# Sheet3.net
KiCad netlist of a schematic drawn in Altium Designer
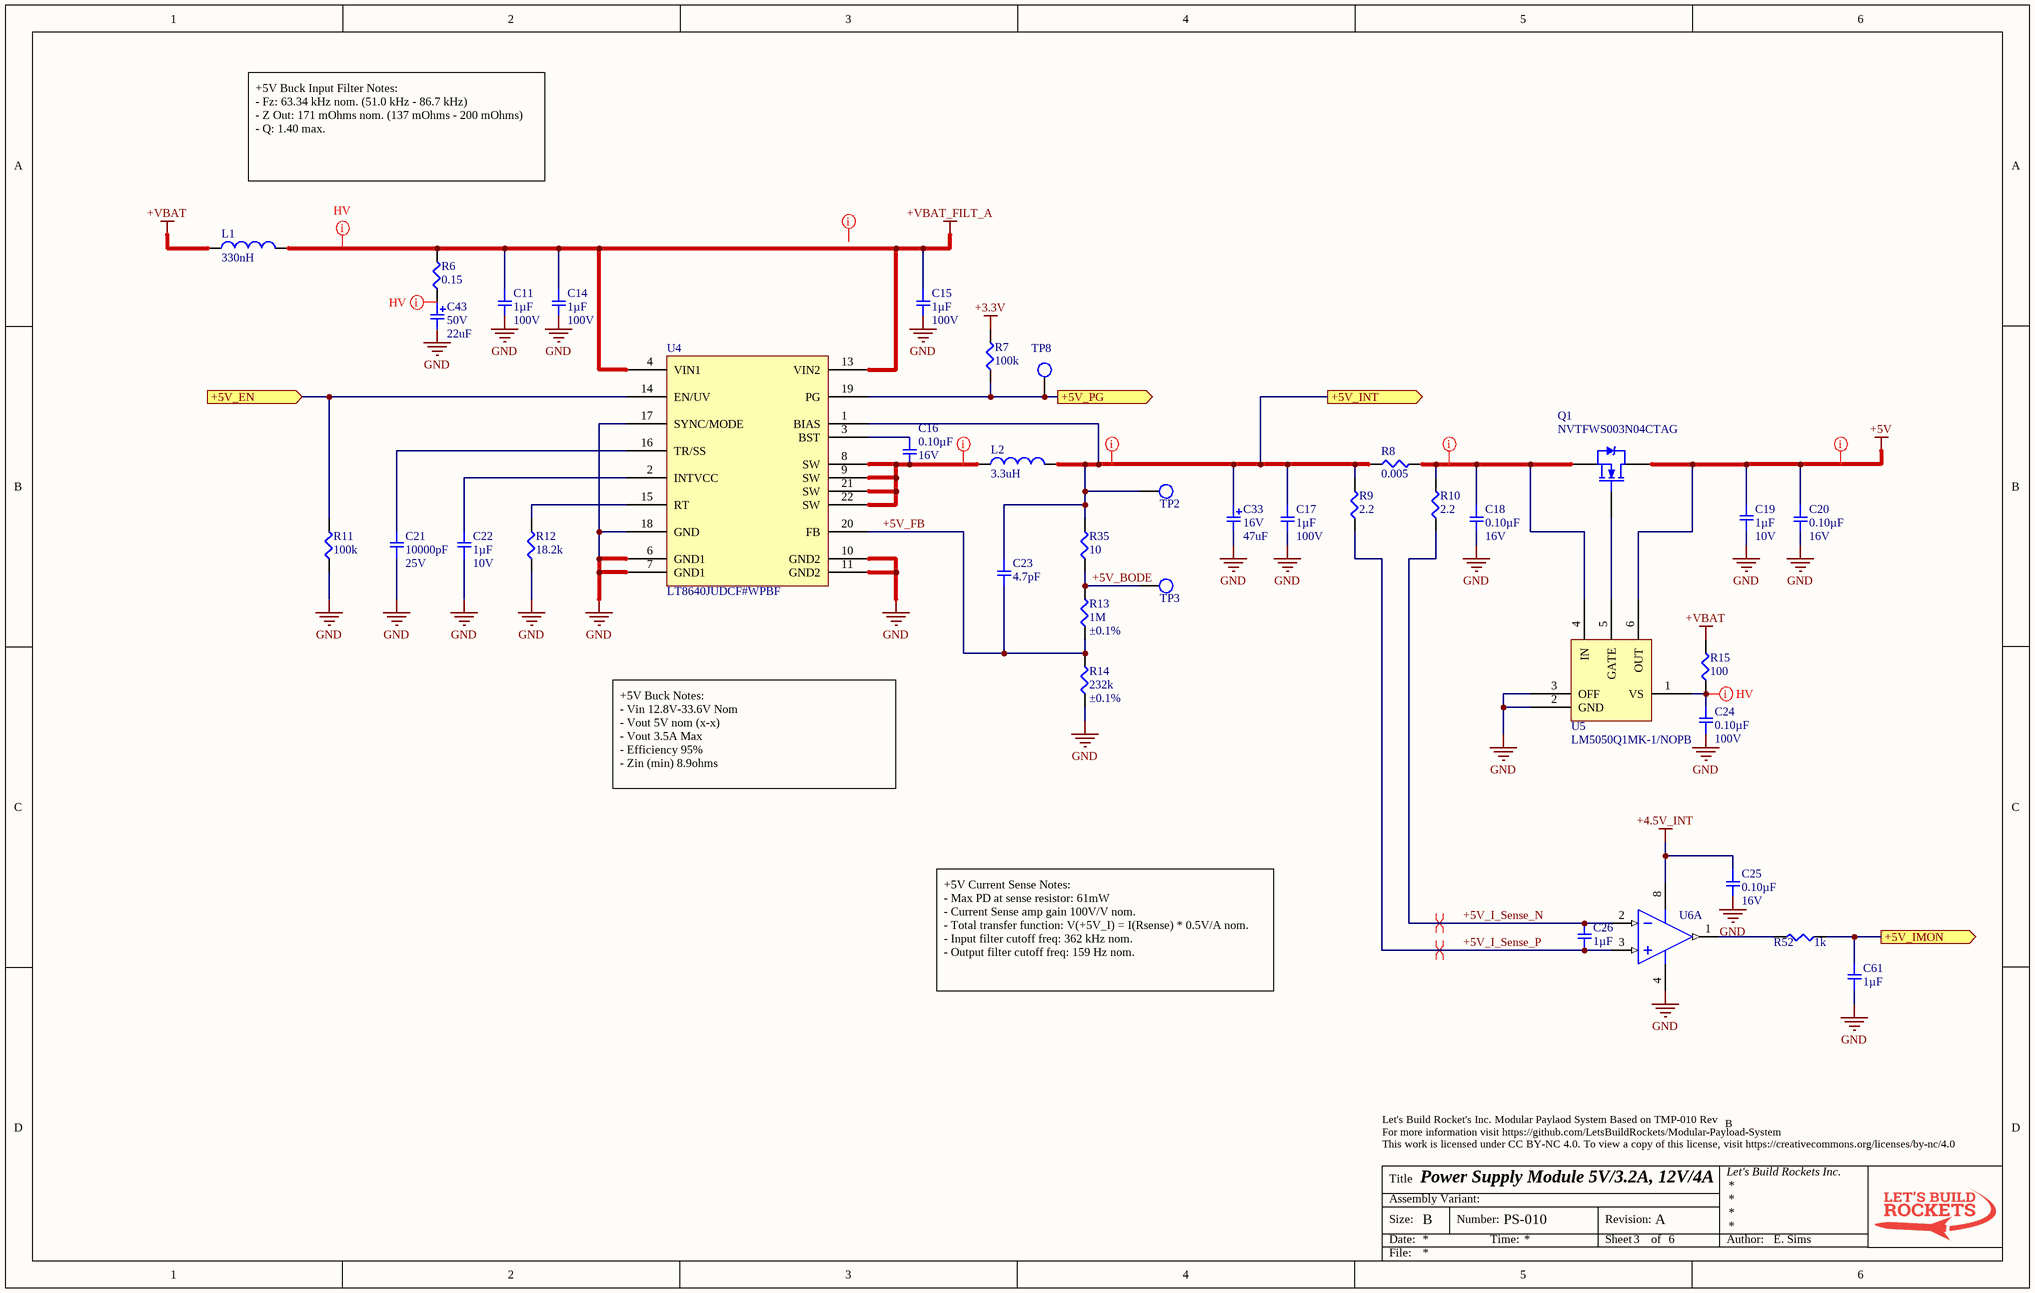
[diagram p0: Sheet3.SchDoc]

(export (version "E")
  (design (tool "Eeschema 10.0.6"))
  (components
    (comp (ref "C11")
      (value "1µF")
      (footprint "SMD-0805C")
      (description "CAP CER 1UF 100V X7S 0805")
      (fields
        (field (name "DIGI-KEY PART NUMBER") "490-10918-1-ND")
        (field (name "PART NUMBER") "GRJ21BC72A105KE11L")
        (field (name "VOLTAGE") "100V")
      )
      (libsource (lib "capacitor_murata_0805") (part "GRJ21BC72A105KE11L"))
    )
    (comp (ref "C14")
      (value "1µF")
      (footprint "SMD-0805C")
      (description "CAP CER 1UF 100V X7S 0805")
      (fields
        (field (name "DIGI-KEY PART NUMBER") "490-10918-1-ND")
        (field (name "PART NUMBER") "GRJ21BC72A105KE11L")
        (field (name "VOLTAGE") "100V")
      )
      (libsource (lib "capacitor_murata_0805") (part "GRJ21BC72A105KE11L"))
    )
    (comp (ref "C15")
      (value "1µF")
      (footprint "SMD-0805C")
      (description "CAP CER 1UF 100V X7S 0805")
      (fields
        (field (name "DIGI-KEY PART NUMBER") "490-10918-1-ND")
        (field (name "PART NUMBER") "GRJ21BC72A105KE11L")
        (field (name "VOLTAGE") "100V")
      )
      (libsource (lib "capacitor_murata_0805") (part "GRJ21BC72A105KE11L"))
    )
    (comp (ref "C16")
      (value "0.10µF")
      (footprint "SMD-0402C")
      (description "CAP CER 0.1UF 16V X7R 0402")
      (fields
        (field (name "DIGI-KEY PART NUMBER") "490-4759-1-ND")
        (field (name "PART NUMBER") "GCM155R71C104KA55D")
        (field (name "VOLTAGE") "16V")
      )
      (libsource (lib "capacitor_murata_0402") (part "GCM155R71C104KA55D"))
    )
    (comp (ref "C17")
      (value "1µF")
      (footprint "SMD-0805C")
      (description "CAP CER 1UF 100V X7S 0805")
      (fields
        (field (name "DIGI-KEY PART NUMBER") "490-10918-1-ND")
        (field (name "PART NUMBER") "GRJ21BC72A105KE11L")
        (field (name "VOLTAGE") "100V")
      )
      (libsource (lib "capacitor_murata_0805") (part "GRJ21BC72A105KE11L"))
    )
    (comp (ref "C18")
      (value "0.10µF")
      (footprint "SMD-0402C")
      (description "CAP CER 0.1UF 16V X7R 0402")
      (fields
        (field (name "DIGI-KEY PART NUMBER") "490-4759-1-ND")
        (field (name "PART NUMBER") "GCM155R71C104KA55D")
        (field (name "VOLTAGE") "16V")
      )
      (libsource (lib "capacitor_murata_0402") (part "GCM155R71C104KA55D"))
    )
    (comp (ref "C19")
      (value "1µF")
      (footprint "SMD-0402C")
      (description "CAP CER 1UF 10V X7S 0402")
      (fields
        (field (name "DIGI-KEY PART NUMBER") "490-13409-1-ND")
        (field (name "PART NUMBER") "GCM155C71A105KE38D")
        (field (name "VOLTAGE") "10V")
      )
      (libsource (lib "capacitor_murata_0402") (part "GCM155C71A105KE38D"))
    )
    (comp (ref "C20")
      (value "0.10µF")
      (footprint "SMD-0402C")
      (description "CAP CER 0.1UF 16V X7R 0402")
      (fields
        (field (name "DIGI-KEY PART NUMBER") "490-4759-1-ND")
        (field (name "PART NUMBER") "GCM155R71C104KA55D")
        (field (name "VOLTAGE") "16V")
      )
      (libsource (lib "capacitor_murata_0402") (part "GCM155R71C104KA55D"))
    )
    (comp (ref "C21")
      (value "10000pF")
      (footprint "SMD-0402C")
      (description "CAP CER 10000PF 25V X7R 0402")
      (fields
        (field (name "DIGI-KEY PART NUMBER") "490-6043-1-ND")
        (field (name "PART NUMBER") "GCM155R71E103KA37D")
        (field (name "VOLTAGE") "25V")
      )
      (libsource (lib "capacitor_murata_0402") (part "GCM155R71E103KA37D"))
    )
    (comp (ref "C22")
      (value "1µF")
      (footprint "SMD-0402C")
      (description "CAP CER 1UF 10V X7S 0402")
      (fields
        (field (name "DIGI-KEY PART NUMBER") "490-13409-1-ND")
        (field (name "PART NUMBER") "GCM155C71A105KE38D")
        (field (name "VOLTAGE") "10V")
      )
      (libsource (lib "capacitor_murata_0402") (part "GCM155C71A105KE38D"))
    )
    (comp (ref "C23")
      (value "4.7pF")
      (footprint "SMD-0402C")
      (description "CAP CER 4.7PF 50V NP0 0402")
      (fields
        (field (name "DIGI-KEY PART NUMBER") "490-12652-1-ND")
        (field (name "PART NUMBER") "GCM1555C1H4R7CA16D")
      )
      (libsource (lib "capacitor_murata_0402") (part "GCM1555C1H4R7CA16D"))
    )
    (comp (ref "C24")
      (value "0.10µF")
      (footprint "SMD-0603C")
      (description "CAP CER 0.1UF 100V X7R 0603")
      (fields
        (field (name "DIGI-KEY PART NUMBER") "490-3285-1-ND")
        (field (name "PART NUMBER") "GRM188R72A104KA35D")
        (field (name "VOLTAGE") "100V")
      )
      (libsource (lib "capacitor_murata_0603") (part "GRM188R72A104KA35D"))
    )
    (comp (ref "C25")
      (value "0.10µF")
      (footprint "SMD-0402C")
      (description "CAP CER 0.1UF 16V X7R 0402")
      (fields
        (field (name "DIGI-KEY PART NUMBER") "490-4759-1-ND")
        (field (name "PART NUMBER") "GCM155R71C104KA55D")
        (field (name "VOLTAGE") "16V")
      )
      (libsource (lib "capacitor_murata_0402") (part "GCM155R71C104KA55D"))
    )
    (comp (ref "C26")
      (value "1µF")
      (footprint "SMD-0402C")
      (description "CAP CER 1UF 10V X7S 0402")
      (fields
        (field (name "DIGI-KEY PART NUMBER") "490-13409-1-ND")
        (field (name "PART NUMBER") "GCM155C71A105KE38D")
      )
      (libsource (lib "capacitor_murata_0402") (part "GCM155C71A105KE38D"))
    )
    (comp (ref "C33")
      (value "47uF")
      (footprint "KEMET W - CAPMP7343X15N")
      (fields (field (name "VOLTAGE") "16V") (field (name "Comment") "T521W476M016ATE045"))
      (libsource (lib "KEMET") (part "T521W476M016ATE045"))
    )
    (comp (ref "C43")
      (value "22uF")
      (footprint "KEMET D - CAPMP7343X31N")
      (fields (field (name "VOLTAGE") "50V") (field (name "Comment") "T521D226M050ATE090"))
      (libsource (lib "KEMET") (part "T521D226M050ATE090"))
    )
    (comp (ref "C61")
      (value "1µF")
      (footprint "SMD-0402C")
      (description "CAP CER 1UF 10V X7S 0402")
      (fields
        (field (name "DIGI-KEY PART NUMBER") "490-13409-1-ND")
        (field (name "PART NUMBER") "GCM155C71A105KE38D")
      )
      (libsource (lib "capacitor_murata_0402") (part "GCM155C71A105KE38D"))
    )
    (comp (ref "L1")
      (value "330nH")
      (footprint "INDM4040X21N (XGL4020)")
      (fields (field (name "Comment") "XGL4020-331ME"))
      (libsource (lib "ModularPayload") (part "XGL4020-331ME"))
    )
    (comp (ref "L2")
      (value "3.3uH")
      (footprint "INDM7050X50N (Wurth)")
      (fields (field (name "TOLERANCE") "20%") (field (name "Comment") "744314330"))
      (libsource (lib "ModularPayload") (part "744314330"))
    )
    (comp (ref "Q1")
      (value "NVTFWS003N04CTAG")
      (footprint "DFN065P305X80-8N")
      (libsource (lib "ModularPayload") (part "NVTFWS003N04CTAG"))
    )
    (comp (ref "R6")
      (value "0.15")
      (footprint "SMD-0603-RES")
      (description "RES SMD 0.15 OHM 5% 1/4W 0603")
      (fields (field (name "PART NUMBER") "ERJ-3BSJR15V") (field (name "DIGI-KEY PART NUMBER") "P17248CT-ND"))
      (libsource (lib "Panasonic_ERJ_0603") (part "ERJ-3BSJR15V"))
    )
    (comp (ref "R7")
      (value "100k")
      (footprint "SMD-0402-RES")
      (description "RES SMD 100K OHM 5% 1/10W 0402")
      (fields (field (name "PART NUMBER") "ERJ-2GEJ104X") (field (name "DIGI-KEY PART NUMBER") "P100KJCT-ND"))
      (libsource (lib "Panasonic_ERJ_0402") (part "ERJ-2GEJ104X"))
    )
    (comp (ref "R8")
      (value "0.005")
      (footprint "SMD-0603-RES")
      (description "RES SMD 0.005 OHM 1% 1/4W 0603")
      (fields
        (field (name "PART NUMBER") "ERJ-3LWFR005V")
        (field (name "DIGI-KEY PART NUMBER") "P19182CT-ND")
      )
      (libsource (lib "Panasonic_ERJ_0603") (part "ERJ-3LWFR005V"))
    )
    (comp (ref "R9")
      (value "2.2")
      (footprint "SMD-0603-RES")
      (description "RES SMD 2.2 OHM 1% 1/10W 0603")
      (fields (field (name "PART NUMBER") "ERJ-3RQF2R2V") (field (name "DIGI-KEY PART NUMBER") "P2.2AJCT-ND"))
      (libsource (lib "Panasonic_ERJ_0603") (part "ERJ-3RQF2R2V"))
    )
    (comp (ref "R10")
      (value "2.2")
      (footprint "SMD-0603-RES")
      (description "RES SMD 2.2 OHM 1% 1/10W 0603")
      (fields (field (name "PART NUMBER") "ERJ-3RQF2R2V") (field (name "DIGI-KEY PART NUMBER") "P2.2AJCT-ND"))
      (libsource (lib "Panasonic_ERJ_0603") (part "ERJ-3RQF2R2V"))
    )
    (comp (ref "R11")
      (value "100k")
      (footprint "SMD-0402-RES")
      (description "RES SMD 100K OHM 5% 1/10W 0402")
      (fields (field (name "PART NUMBER") "ERJ-2GEJ104X") (field (name "DIGI-KEY PART NUMBER") "P100KJCT-ND"))
      (libsource (lib "Panasonic_ERJ_0402") (part "ERJ-2GEJ104X"))
    )
    (comp (ref "R12")
      (value "18.2k")
      (footprint "SMD-0402-RES")
      (description "RES SMD 18.2K OHM 1% 1/10W 0402")
      (fields
        (field (name "PART NUMBER") "ERJ-2RKF1822X")
        (field (name "DIGI-KEY PART NUMBER") "P18.2KLCT-ND")
      )
      (libsource (lib "Panasonic_ERJ_0402") (part "ERJ-2RKF1822X"))
    )
    (comp (ref "R13")
      (value "1M")
      (footprint "SMD-0805-RES")
      (description "RES SMD 1M OHM 0.1% 1/4W 0805")
      (fields
        (field (name "PART NUMBER") "ERJ-PB6B1004V")
        (field (name "DIGI-KEY PART NUMBER") "P20936CT-ND")
        (field (name "TOLERANCE") "±0.1%")
      )
      (libsource (lib "Panasonic_ERJ_0805") (part "ERJ-PB6B1004V"))
    )
    (comp (ref "R14")
      (value "232k")
      (footprint "SMD-0805-RES")
      (description "RES SMD 232K OHM 0.1% 1/4W 0805")
      (fields
        (field (name "PART NUMBER") "ERJ-PB6B2323V")
        (field (name "DIGI-KEY PART NUMBER") "P20861CT-ND")
        (field (name "TOLERANCE") "±0.1%")
      )
      (libsource (lib "Panasonic_ERJ_0805") (part "ERJ-PB6B2323V"))
    )
    (comp (ref "R15")
      (value "100")
      (footprint "SMD-0402-RES")
      (description "RES SMD 100 OHM 5% 1/10W 0402")
      (fields (field (name "PART NUMBER") "ERJ-2GEJ101X") (field (name "DIGI-KEY PART NUMBER") "P100JCT-ND"))
      (libsource (lib "Panasonic_ERJ_0402") (part "ERJ-2GEJ101X"))
    )
    (comp (ref "R35")
      (value "10")
      (footprint "SMD-0402-RES")
      (description "RES SMD 10 OHM 5% 1/10W 0402")
      (fields (field (name "PART NUMBER") "ERJ-2GEJ100X") (field (name "DIGI-KEY PART NUMBER") "P10JCT-ND"))
      (libsource (lib "Panasonic_ERJ_0402") (part "ERJ-2GEJ100X"))
    )
    (comp (ref "R52")
      (value "1k")
      (footprint "SMD-0402-RES")
      (description "RES SMD 1K OHM 5% 1/10W 0402")
      (fields (field (name "PART NUMBER") "ERJ-2GEJ102X") (field (name "DIGI-KEY PART NUMBER") "P1.0KJCT-ND"))
      (libsource (lib "Panasonic_ERJ_0402") (part "ERJ-2GEJ102X"))
    )
    (comp (ref "TP2") (value "TP") (footprint "TP_SMD_40") (libsource (lib "TP") (part "TP")))
    (comp (ref "TP3") (value "TP") (footprint "TP_SMD_40") (libsource (lib "TP") (part "TP")))
    (comp (ref "TP8") (value "TP") (footprint "TP_SMD_40") (libsource (lib "TP") (part "TP")))
    (comp (ref "U4")
      (value "LT8640JUDCF#WPBF")
      (footprint "QFN50P300X400X80_HS-21N (LT8640)")
      (libsource (lib "ModularPayload") (part "LT8640JUDCF#WPBF"))
    )
    (comp (ref "U5")
      (value "LM5050Q1MK-1/NOPB")
      (footprint "SOT95P280X110-6N")
      (libsource (lib "ModularPayload") (part "LM5050Q1MK-1/NOPB"))
    )
    (comp (ref "U6")
      (value "INA2180A3IDGKT")
      (footprint "TSOP65P490X110-8N")
      (libsource (lib "ModularPayload") (part "INA2180A3IDGKT"))
    )
  )
  (nets
    (net (code "1") (name "+3.3V") (class "Default")
      (node (ref "R7") (pin "2") (pinfunction "2_2") (pintype "passive"))
    )
    (net (code "2") (name "+4.5V_INT") (class "Default")
      (node (ref "C25") (pin "1") (pinfunction "1_1") (pintype "passive"))
      (node (ref "U6") (pin "8") (pinfunction "VS_8") (pintype "power_in"))
    )
    (net (code "3") (name "+5V") (class "Default")
      (node (ref "C19") (pin "2") (pinfunction "2_2") (pintype "passive"))
      (node (ref "C20") (pin "1") (pinfunction "1_1") (pintype "passive"))
      (node (ref "Q1") (pin "D") (pinfunction "D_D") (pintype "passive"))
      (node (ref "U5") (pin "6") (pinfunction "OUT_6") (pintype "passive"))
    )
    (net (code "4") (name "+VBAT") (class "Default")
      (node (ref "L1") (pin "1") (pinfunction "1_1") (pintype "passive"))
      (node (ref "R15") (pin "2") (pinfunction "2_2") (pintype "passive"))
    )
    (net (code "5") (name "+VBAT_FILT_A") (class "Default")
      (node (ref "C11") (pin "1") (pinfunction "1_1") (pintype "passive"))
      (node (ref "C14") (pin "1") (pinfunction "1_1") (pintype "passive"))
      (node (ref "C15") (pin "1") (pinfunction "1_1") (pintype "passive"))
      (node (ref "L1") (pin "2") (pinfunction "2_2") (pintype "passive"))
      (node (ref "R6") (pin "2") (pinfunction "2_2") (pintype "passive"))
      (node (ref "U4") (pin "13") (pinfunction "VIN2_13") (pintype "passive"))
      (node (ref "U4") (pin "4") (pinfunction "VIN1_4") (pintype "passive"))
    )
    (net (code "6") (name "/+5V_BODE") (class "Default")
      (node (ref "R13") (pin "2") (pinfunction "2_2") (pintype "passive"))
      (node (ref "R35") (pin "1") (pinfunction "1_1") (pintype "passive"))
      (node (ref "TP3") (pin "1") (pintype "passive"))
    )
    (net (code "7") (name "/+5V_EN") (class "Default")
      (node (ref "R11") (pin "2") (pinfunction "2_2") (pintype "passive"))
      (node (ref "U4") (pin "14") (pinfunction "EN/UV_14") (pintype "passive"))
    )
    (net (code "8") (name "/+5V_FB") (class "Default")
      (node (ref "C23") (pin "2") (pinfunction "2_2") (pintype "passive"))
      (node (ref "R13") (pin "1") (pinfunction "1_1") (pintype "passive"))
      (node (ref "R14") (pin "2") (pinfunction "2_2") (pintype "passive"))
      (node (ref "U4") (pin "20") (pinfunction "FB_20") (pintype "passive"))
    )
    (net (code "9") (name "/+5V_IMON") (class "Default")
      (node (ref "C61") (pin "2") (pinfunction "2_2") (pintype "passive"))
      (node (ref "R52") (pin "1") (pinfunction "1_1") (pintype "passive"))
    )
    (net (code "10") (name "/+5V_INT") (class "Default")
      (node (ref "C17") (pin "1") (pinfunction "1_1") (pintype "passive"))
      (node (ref "C23") (pin "1") (pinfunction "1_1") (pintype "passive"))
      (node (ref "C33") (pin "1") (pinfunction "1_1") (pintype "passive"))
      (node (ref "L2") (pin "2") (pinfunction "2_2") (pintype "passive"))
      (node (ref "R35") (pin "2") (pinfunction "2_2") (pintype "passive"))
      (node (ref "R8") (pin "1") (pinfunction "1_1") (pintype "passive"))
      (node (ref "R9") (pin "2") (pinfunction "2_2") (pintype "passive"))
      (node (ref "TP2") (pin "1") (pintype "passive"))
      (node (ref "U4") (pin "1") (pinfunction "BIAS_1") (pintype "passive"))
    )
    (net (code "11") (name "/+5V_I_Sense_N") (class "Default")
      (node (ref "C26") (pin "2") (pinfunction "2_2") (pintype "passive"))
      (node (ref "R10") (pin "1") (pinfunction "1_1") (pintype "passive"))
      (node (ref "U6") (pin "2") (pinfunction "IN-1_2") (pintype "input"))
    )
    (net (code "12") (name "/+5V_I_Sense_P") (class "Default")
      (node (ref "C26") (pin "1") (pinfunction "1_1") (pintype "passive"))
      (node (ref "R9") (pin "1") (pinfunction "1_1") (pintype "passive"))
      (node (ref "U6") (pin "3") (pinfunction "IN+1_3") (pintype "input"))
    )
    (net (code "13") (name "/+5V_PG") (class "Default")
      (node (ref "R7") (pin "1") (pinfunction "1_1") (pintype "passive"))
      (node (ref "TP8") (pin "1") (pintype "passive"))
      (node (ref "U4") (pin "19") (pinfunction "PG_19") (pintype "passive"))
    )
    (net (code "14") (name "GND") (class "Default")
      (node (ref "C11") (pin "2") (pinfunction "2_2") (pintype "passive"))
      (node (ref "C14") (pin "2") (pinfunction "2_2") (pintype "passive"))
      (node (ref "C15") (pin "2") (pinfunction "2_2") (pintype "passive"))
      (node (ref "C17") (pin "2") (pinfunction "2_2") (pintype "passive"))
      (node (ref "C18") (pin "2") (pinfunction "2_2") (pintype "passive"))
      (node (ref "C19") (pin "1") (pinfunction "1_1") (pintype "passive"))
      (node (ref "C20") (pin "2") (pinfunction "2_2") (pintype "passive"))
      (node (ref "C21") (pin "1") (pinfunction "1_1") (pintype "passive"))
      (node (ref "C22") (pin "1") (pinfunction "1_1") (pintype "passive"))
      (node (ref "C24") (pin "1") (pinfunction "1_1") (pintype "passive"))
      (node (ref "C25") (pin "2") (pinfunction "2_2") (pintype "passive"))
      (node (ref "C33") (pin "2") (pinfunction "2_2") (pintype "passive"))
      (node (ref "C43") (pin "2") (pinfunction "2_2") (pintype "passive"))
      (node (ref "C61") (pin "1") (pinfunction "1_1") (pintype "passive"))
      (node (ref "R11") (pin "1") (pinfunction "1_1") (pintype "passive"))
      (node (ref "R12") (pin "1") (pinfunction "1_1") (pintype "passive"))
      (node (ref "R14") (pin "1") (pinfunction "1_1") (pintype "passive"))
      (node (ref "U4") (pin "10") (pinfunction "GND2_10") (pintype "passive"))
      (node (ref "U4") (pin "11") (pinfunction "GND2_11") (pintype "passive"))
      (node (ref "U4") (pin "17") (pinfunction "SYNC/MODE_17") (pintype "passive"))
      (node (ref "U4") (pin "18") (pinfunction "GND_18") (pintype "passive"))
      (node (ref "U4") (pin "6") (pinfunction "GND1_6") (pintype "passive"))
      (node (ref "U4") (pin "7") (pinfunction "GND1_7") (pintype "passive"))
      (node (ref "U5") (pin "2") (pinfunction "GND_2") (pintype "passive"))
      (node (ref "U5") (pin "3") (pinfunction "OFF_3") (pintype "passive"))
      (node (ref "U6") (pin "4") (pinfunction "GND_4") (pintype "power_in"))
    )
    (net (code "15") (name "Net-(C16-Pad2)") (class "Default")
      (node (ref "C16") (pin "2") (pinfunction "2_2") (pintype "passive"))
      (node (ref "L2") (pin "1") (pinfunction "1_1") (pintype "passive"))
      (node (ref "U4") (pin "21") (pinfunction "SW_21") (pintype "passive"))
      (node (ref "U4") (pin "22") (pinfunction "SW_22") (pintype "passive"))
      (node (ref "U4") (pin "8") (pinfunction "SW_8") (pintype "passive"))
      (node (ref "U4") (pin "9") (pinfunction "SW_9") (pintype "passive"))
    )
    (net (code "16") (name "Net-(C43-Pad1)") (class "Default")
      (node (ref "C43") (pin "1") (pinfunction "1_1") (pintype "passive"))
      (node (ref "R6") (pin "1") (pinfunction "1_1") (pintype "passive"))
    )
    (net (code "17") (name "Net-(U4-BST)") (class "Default")
      (node (ref "C16") (pin "1") (pinfunction "1_1") (pintype "passive"))
      (node (ref "U4") (pin "3") (pinfunction "BST_3") (pintype "passive"))
    )
    (net (code "18") (name "Net-(U4-INTVCC)") (class "Default")
      (node (ref "C22") (pin "2") (pinfunction "2_2") (pintype "passive"))
      (node (ref "U4") (pin "2") (pinfunction "INTVCC_2") (pintype "passive"))
    )
    (net (code "19") (name "Net-(U4-RT)") (class "Default")
      (node (ref "R12") (pin "2") (pinfunction "2_2") (pintype "passive"))
      (node (ref "U4") (pin "15") (pinfunction "RT_15") (pintype "passive"))
    )
    (net (code "20") (name "Net-(U4-TR{slash}SS)") (class "Default")
      (node (ref "C21") (pin "2") (pinfunction "2_2") (pintype "passive"))
      (node (ref "U4") (pin "16") (pinfunction "TR/SS_16") (pintype "passive"))
    )
    (net (code "21") (name "Net-(U5-GATE)") (class "Default")
      (node (ref "Q1") (pin "G") (pinfunction "G_G") (pintype "passive"))
      (node (ref "U5") (pin "5") (pinfunction "GATE_5") (pintype "passive"))
    )
    (net (code "22") (name "Net-(U5-IN)") (class "Default")
      (node (ref "C18") (pin "1") (pinfunction "1_1") (pintype "passive"))
      (node (ref "Q1") (pin "S") (pinfunction "S_S") (pintype "passive"))
      (node (ref "R10") (pin "2") (pinfunction "2_2") (pintype "passive"))
      (node (ref "R8") (pin "2") (pinfunction "2_2") (pintype "passive"))
      (node (ref "U5") (pin "4") (pinfunction "IN_4") (pintype "passive"))
    )
    (net (code "23") (name "Net-(U5-VS)") (class "Default")
      (node (ref "C24") (pin "2") (pinfunction "2_2") (pintype "passive"))
      (node (ref "R15") (pin "1") (pinfunction "1_1") (pintype "passive"))
      (node (ref "U5") (pin "1") (pinfunction "VS_1") (pintype "passive"))
    )
    (net (code "24") (name "Net-(U6A-OUT1)") (class "Default")
      (node (ref "R52") (pin "2") (pinfunction "2_2") (pintype "passive"))
      (node (ref "U6") (pin "1") (pinfunction "OUT1_1") (pintype "output"))
    )
  )
)
